# Main.net
KiCad netlist of a schematic drawn in Altium Designer
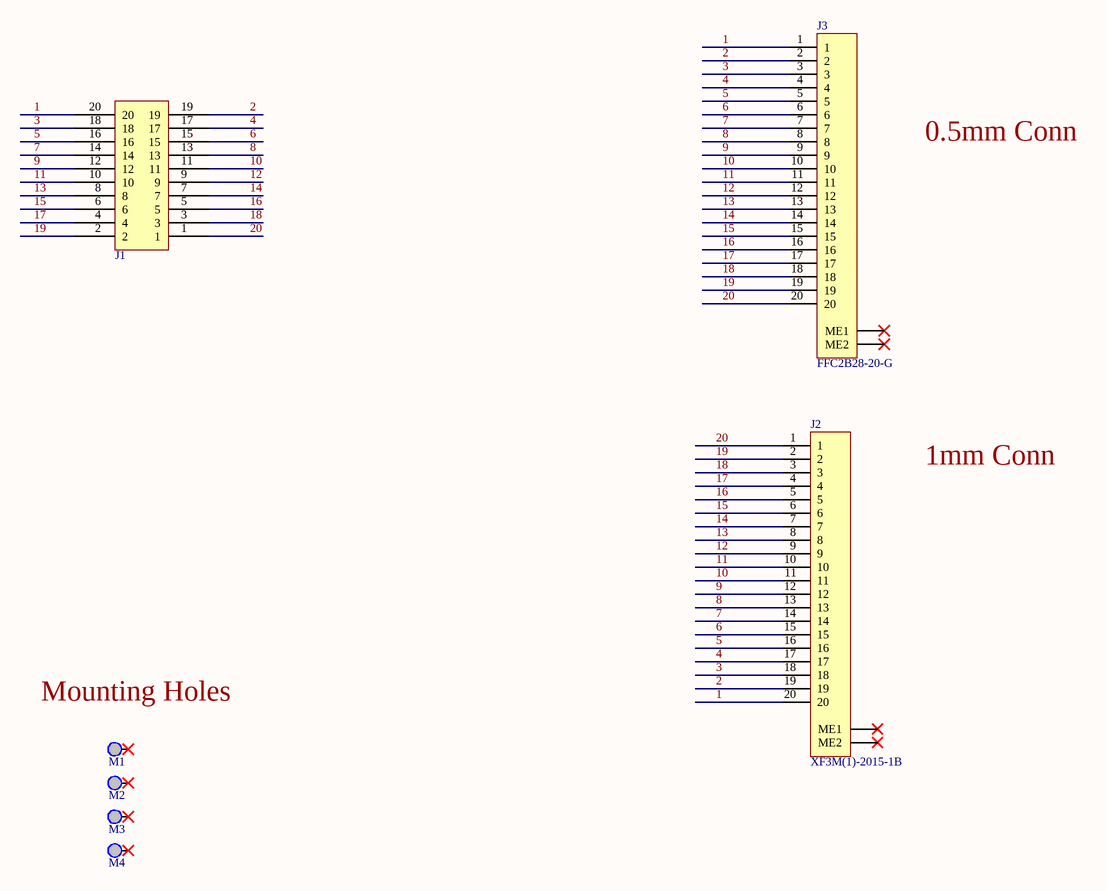
[diagram p0: Main.SchDoc]

(export (version "E")
  (design (tool "Eeschema 10.0.6"))
  (components
    (comp (ref "J1")
      (value "SBH11-PBPC-D10-ST-BK")
      (footprint "HDR-V-2x10-KEYED")
      (description "CONN HEADER VERT 20POS 2.54MM")
      (libsource (lib "intercreate") (part "HDR-V-2x10-M"))
    )
    (comp (ref "J2")
      (value "XF3M(1)-2015-1B")
      (footprint "CONN-FFC-H-20P-1MM")
      (description "1.0-mm Pitch, Dual Contact ; For FPC/FFC, 20 Contacts, RoHS")
      (libsource (lib "intercreate") (part "CONN-FFC-H-20P-1MM"))
    )
    (comp (ref "J3")
      (value "FFC2B28-20-G")
      (footprint "CONN-FFC-H-20P-0.5MM")
      (description "20W, 0.5MM Ffc Con, R/a, Dual Cont,")
      (libsource (lib "intercreate") (part "CONN-FFC-H-20P-0.5MM"))
    )
    (comp (ref "M1")
      (value "MTG_HOLE")
      (footprint "MH_P_2.5MM")
      (description "MTG HOLE PLATED VARIOUS SIZES")
      (libsource (lib "intercreate") (part "MTG_HOLE"))
    )
    (comp (ref "M2")
      (value "MTG_HOLE")
      (footprint "MH_P_2.5MM")
      (description "MTG HOLE PLATED VARIOUS SIZES")
      (libsource (lib "intercreate") (part "MTG_HOLE"))
    )
    (comp (ref "M3")
      (value "MTG_HOLE")
      (footprint "MH_P_2.5MM")
      (description "MTG HOLE PLATED VARIOUS SIZES")
      (libsource (lib "intercreate") (part "MTG_HOLE"))
    )
    (comp (ref "M4")
      (value "MTG_HOLE")
      (footprint "MH_P_2.5MM")
      (description "MTG HOLE PLATED VARIOUS SIZES")
      (libsource (lib "intercreate") (part "MTG_HOLE"))
    )
  )
  (nets
    (net (code "1") (name "/1") (class "Default")
      (node (ref "J1") (pin "20") (pinfunction "20_20") (pintype "power_in"))
      (node (ref "J2") (pin "20") (pinfunction "20_20") (pintype "passive"))
      (node (ref "J3") (pin "1") (pinfunction "1_1") (pintype "passive"))
    )
    (net (code "2") (name "/2") (class "Default")
      (node (ref "J1") (pin "19") (pinfunction "19_19") (pintype "power_in"))
      (node (ref "J2") (pin "19") (pinfunction "19_19") (pintype "passive"))
      (node (ref "J3") (pin "2") (pinfunction "2_2") (pintype "passive"))
    )
    (net (code "3") (name "/3") (class "Default")
      (node (ref "J1") (pin "18") (pinfunction "18_18") (pintype "power_in"))
      (node (ref "J2") (pin "18") (pinfunction "18_18") (pintype "passive"))
      (node (ref "J3") (pin "3") (pinfunction "3_3") (pintype "passive"))
    )
    (net (code "4") (name "/4") (class "Default")
      (node (ref "J1") (pin "17") (pinfunction "17_17") (pintype "power_in"))
      (node (ref "J2") (pin "17") (pinfunction "17_17") (pintype "passive"))
      (node (ref "J3") (pin "4") (pinfunction "4_4") (pintype "passive"))
    )
    (net (code "5") (name "/5") (class "Default")
      (node (ref "J1") (pin "16") (pinfunction "16_16") (pintype "power_in"))
      (node (ref "J2") (pin "16") (pinfunction "16_16") (pintype "passive"))
      (node (ref "J3") (pin "5") (pinfunction "5_5") (pintype "passive"))
    )
    (net (code "6") (name "/6") (class "Default")
      (node (ref "J1") (pin "15") (pinfunction "15_15") (pintype "power_in"))
      (node (ref "J2") (pin "15") (pinfunction "15_15") (pintype "passive"))
      (node (ref "J3") (pin "6") (pinfunction "6_6") (pintype "passive"))
    )
    (net (code "7") (name "/7") (class "Default")
      (node (ref "J1") (pin "14") (pinfunction "14_14") (pintype "power_in"))
      (node (ref "J2") (pin "14") (pinfunction "14_14") (pintype "passive"))
      (node (ref "J3") (pin "7") (pinfunction "7_7") (pintype "passive"))
    )
    (net (code "8") (name "/8") (class "Default")
      (node (ref "J1") (pin "13") (pinfunction "13_13") (pintype "power_in"))
      (node (ref "J2") (pin "13") (pinfunction "13_13") (pintype "passive"))
      (node (ref "J3") (pin "8") (pinfunction "8_8") (pintype "passive"))
    )
    (net (code "9") (name "/9") (class "Default")
      (node (ref "J1") (pin "12") (pinfunction "12_12") (pintype "power_in"))
      (node (ref "J2") (pin "12") (pinfunction "12_12") (pintype "passive"))
      (node (ref "J3") (pin "9") (pinfunction "9_9") (pintype "passive"))
    )
    (net (code "10") (name "/10") (class "Default")
      (node (ref "J1") (pin "11") (pinfunction "11_11") (pintype "power_in"))
      (node (ref "J2") (pin "11") (pinfunction "11_11") (pintype "passive"))
      (node (ref "J3") (pin "10") (pinfunction "10_10") (pintype "passive"))
    )
    (net (code "11") (name "/11") (class "Default")
      (node (ref "J1") (pin "10") (pinfunction "10_10") (pintype "passive"))
      (node (ref "J2") (pin "10") (pinfunction "10_10") (pintype "passive"))
      (node (ref "J3") (pin "11") (pinfunction "11_11") (pintype "passive"))
    )
    (net (code "12") (name "/12") (class "Default")
      (node (ref "J1") (pin "9") (pinfunction "9_9") (pintype "passive"))
      (node (ref "J2") (pin "9") (pinfunction "9_9") (pintype "passive"))
      (node (ref "J3") (pin "12") (pinfunction "12_12") (pintype "passive"))
    )
    (net (code "13") (name "/13") (class "Default")
      (node (ref "J1") (pin "8") (pinfunction "8_8") (pintype "passive"))
      (node (ref "J2") (pin "8") (pinfunction "8_8") (pintype "passive"))
      (node (ref "J3") (pin "13") (pinfunction "13_13") (pintype "passive"))
    )
    (net (code "14") (name "/14") (class "Default")
      (node (ref "J1") (pin "7") (pinfunction "7_7") (pintype "passive"))
      (node (ref "J2") (pin "7") (pinfunction "7_7") (pintype "passive"))
      (node (ref "J3") (pin "14") (pinfunction "14_14") (pintype "passive"))
    )
    (net (code "15") (name "/15") (class "Default")
      (node (ref "J1") (pin "6") (pinfunction "6_6") (pintype "passive"))
      (node (ref "J2") (pin "6") (pinfunction "6_6") (pintype "passive"))
      (node (ref "J3") (pin "15") (pinfunction "15_15") (pintype "passive"))
    )
    (net (code "16") (name "/16") (class "Default")
      (node (ref "J1") (pin "5") (pinfunction "5_5") (pintype "passive"))
      (node (ref "J2") (pin "5") (pinfunction "5_5") (pintype "passive"))
      (node (ref "J3") (pin "16") (pinfunction "16_16") (pintype "passive"))
    )
    (net (code "17") (name "/17") (class "Default")
      (node (ref "J1") (pin "4") (pinfunction "4_4") (pintype "passive"))
      (node (ref "J2") (pin "4") (pinfunction "4_4") (pintype "passive"))
      (node (ref "J3") (pin "17") (pinfunction "17_17") (pintype "passive"))
    )
    (net (code "18") (name "/18") (class "Default")
      (node (ref "J1") (pin "3") (pinfunction "3_3") (pintype "passive"))
      (node (ref "J2") (pin "3") (pinfunction "3_3") (pintype "passive"))
      (node (ref "J3") (pin "18") (pinfunction "18_18") (pintype "passive"))
    )
    (net (code "19") (name "/19") (class "Default")
      (node (ref "J1") (pin "2") (pinfunction "2_2") (pintype "passive"))
      (node (ref "J2") (pin "2") (pinfunction "2_2") (pintype "passive"))
      (node (ref "J3") (pin "19") (pinfunction "19_19") (pintype "passive"))
    )
    (net (code "20") (name "/20") (class "Default")
      (node (ref "J1") (pin "1") (pinfunction "1_1") (pintype "passive"))
      (node (ref "J2") (pin "1") (pinfunction "1_1") (pintype "passive"))
      (node (ref "J3") (pin "20") (pinfunction "20_20") (pintype "passive"))
    )
    (net (code "21") (name "unconnected-(J2-PadME1)") (class "Default")
      (node (ref "J2") (pin "ME1") (pinfunction "ME1_ME1") (pintype "passive+no_connect"))
    )
    (net (code "22") (name "unconnected-(J2-PadME2)") (class "Default")
      (node (ref "J2") (pin "ME2") (pinfunction "ME2_ME2") (pintype "passive+no_connect"))
    )
    (net (code "23") (name "unconnected-(J3-PadME1)") (class "Default")
      (node (ref "J3") (pin "ME1") (pinfunction "ME1_ME1") (pintype "passive+no_connect"))
    )
    (net (code "24") (name "unconnected-(J3-PadME2)") (class "Default")
      (node (ref "J3") (pin "ME2") (pinfunction "ME2_ME2") (pintype "passive+no_connect"))
    )
    (net (code "25") (name "unconnected-(M1-Pad1)") (class "Default")
      (node (ref "M1") (pin "1") (pinfunction "1_1") (pintype "passive+no_connect"))
    )
    (net (code "26") (name "unconnected-(M2-Pad1)") (class "Default")
      (node (ref "M2") (pin "1") (pinfunction "1_1") (pintype "passive+no_connect"))
    )
    (net (code "27") (name "unconnected-(M3-Pad1)") (class "Default")
      (node (ref "M3") (pin "1") (pinfunction "1_1") (pintype "passive+no_connect"))
    )
    (net (code "28") (name "unconnected-(M4-Pad1)") (class "Default")
      (node (ref "M4") (pin "1") (pinfunction "1_1") (pintype "passive+no_connect"))
    )
  )
)
